# Sheet_CL-TPI-01.net
KiCad netlist of a schematic drawn in Altium Designer
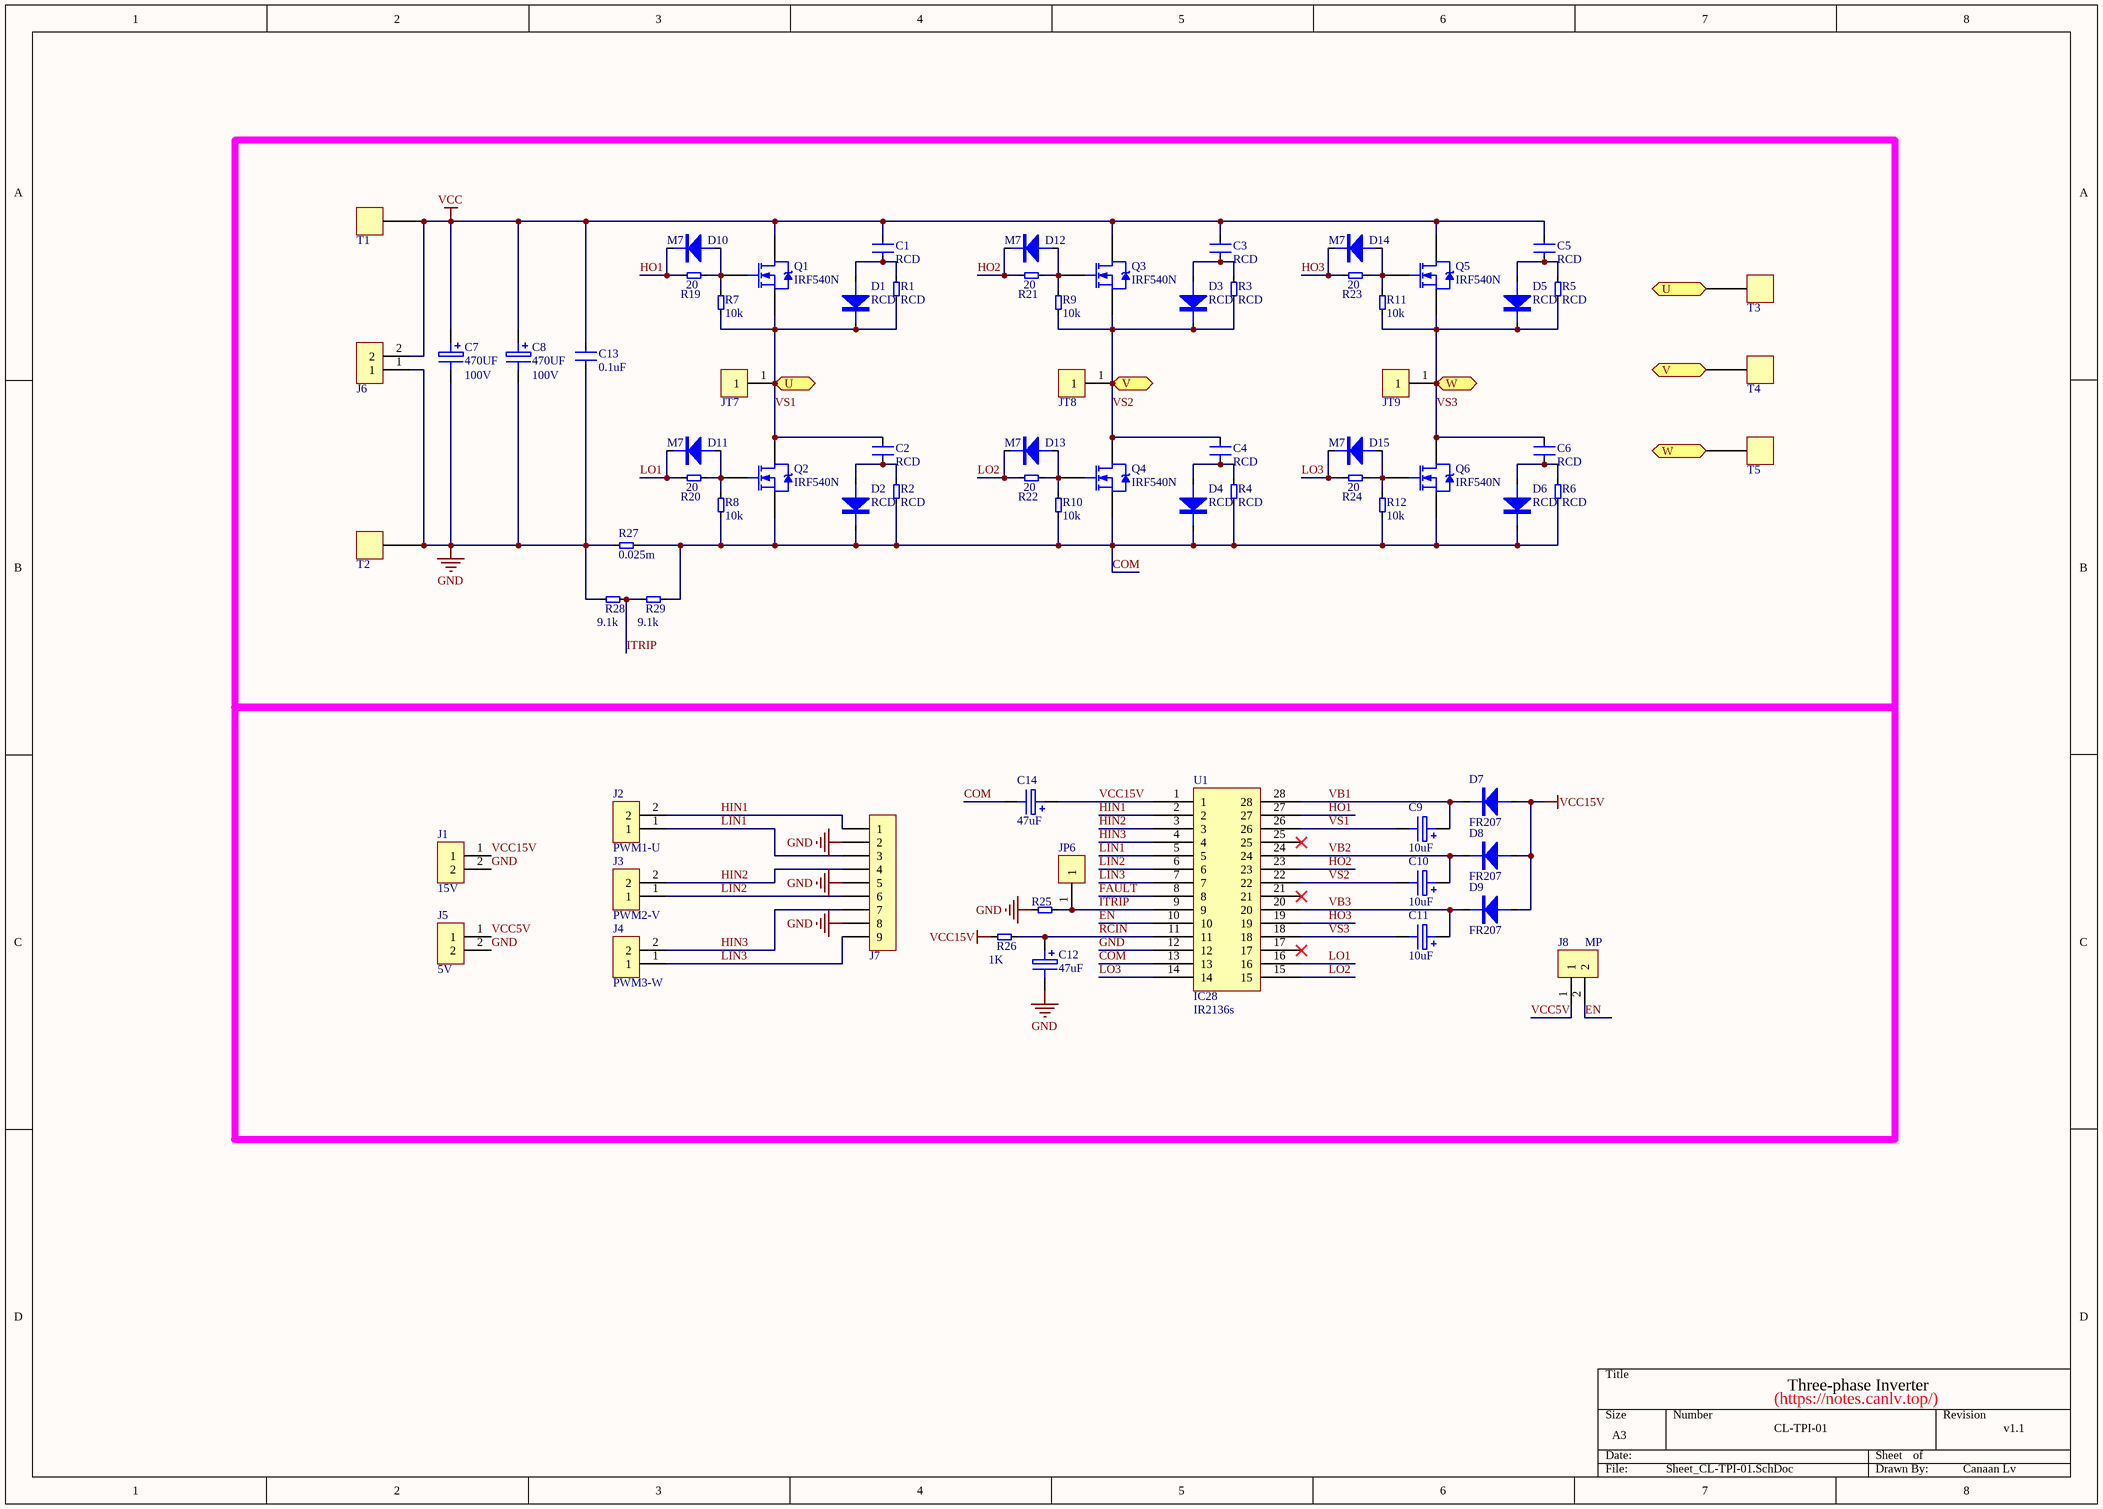
[diagram p0: Sheet_CL-TPI-01.SchDoc]

(export (version "E")
  (design (tool "Eeschema 10.0.6"))
  (components
    (comp (ref "C1") (value "RCD") (footprint "C0805") (libsource (lib "电容") (part "C贴片电容")))
    (comp (ref "C2") (value "RCD") (footprint "C0805") (libsource (lib "电容") (part "C贴片电容")))
    (comp (ref "C3") (value "RCD") (footprint "C0805") (libsource (lib "电容") (part "C贴片电容")))
    (comp (ref "C4") (value "RCD") (footprint "C0805") (libsource (lib "电容") (part "C贴片电容")))
    (comp (ref "C5") (value "RCD") (footprint "C0805") (libsource (lib "电容") (part "C贴片电容")))
    (comp (ref "C6") (value "RCD") (footprint "C0805") (libsource (lib "电容") (part "C贴片电容")))
    (comp (ref "C7")
      (value "470UF")
      (footprint "CZ16X25")
      (fields (field (name "ALTIUM_UNNAMED_1") "100V"))
      (libsource (lib "电容") (part "C直插电容"))
    )
    (comp (ref "C8")
      (value "470UF")
      (footprint "CZ16X25")
      (fields (field (name "ALTIUM_UNNAMED_1") "100V"))
      (libsource (lib "电容") (part "C直插电容"))
    )
    (comp (ref "C9") (value "10uF") (footprint "CZ0.50/25V47U") (libsource (lib "电容") (part "C直插电容")))
    (comp (ref "C10") (value "10uF") (footprint "CZ0.50/25V47U") (libsource (lib "电容") (part "C直插电容")))
    (comp (ref "C11") (value "10uF") (footprint "CZ0.50/25V47U") (libsource (lib "电容") (part "C直插电容")))
    (comp (ref "C12") (value "47uF") (footprint "CZ0.50/25V47U") (libsource (lib "电容") (part "C直插电容")))
    (comp (ref "C13") (value "0.1uF") (footprint "C0805") (libsource (lib "电容") (part "C贴片电容")))
    (comp (ref "C14") (value "47uF") (footprint "CZ0.50/25V47U") (libsource (lib "电容") (part "C直插电容")))
    (comp (ref "D1") (value "RCD") (footprint "SMA-1") (libsource (lib "二极管") (part "0805D")))
    (comp (ref "D2") (value "RCD") (footprint "SMA-1") (libsource (lib "二极管") (part "0805D")))
    (comp (ref "D3") (value "RCD") (footprint "SMA-1") (libsource (lib "二极管") (part "0805D")))
    (comp (ref "D4") (value "RCD") (footprint "SMA-1") (libsource (lib "二极管") (part "0805D")))
    (comp (ref "D5") (value "RCD") (footprint "SMA-1") (libsource (lib "二极管") (part "0805D")))
    (comp (ref "D6") (value "RCD") (footprint "SMA-1") (libsource (lib "二极管") (part "0805D")))
    (comp (ref "D7") (value "FR207") (footprint "DO-41-2") (libsource (lib "二极管") (part "DO-41")))
    (comp (ref "D8") (value "FR207") (footprint "DO-41-2") (libsource (lib "二极管") (part "DO-41")))
    (comp (ref "D9") (value "FR207") (footprint "DO-41-2") (libsource (lib "二极管") (part "DO-41")))
    (comp (ref "D10") (value "M7") (footprint "SMA-1") (libsource (lib "") (part "0805D_1")))
    (comp (ref "D11") (value "M7") (footprint "SMA-1") (libsource (lib "") (part "0805D_1")))
    (comp (ref "D12") (value "M7") (footprint "SMA-1") (libsource (lib "") (part "0805D_1")))
    (comp (ref "D13") (value "M7") (footprint "SMA-1") (libsource (lib "") (part "0805D_1")))
    (comp (ref "D14") (value "M7") (footprint "SMA-1") (libsource (lib "") (part "0805D_1")))
    (comp (ref "D15") (value "M7") (footprint "SMA-1") (libsource (lib "") (part "0805D_1")))
    (comp (ref "J1") (value "15V") (footprint "2.54XH接插件2P") (libsource (lib "") (part "SIP-2_2")))
    (comp (ref "J2") (value "PWM1-U") (footprint "2.54XH接插件2P") (libsource (lib "接插件") (part "SIP-2")))
    (comp (ref "J3") (value "PWM2-V") (footprint "2.54XH接插件2P") (libsource (lib "接插件") (part "SIP-2")))
    (comp (ref "J4") (value "PWM3-W") (footprint "2.54XH接插件2P") (libsource (lib "接插件") (part "SIP-2")))
    (comp (ref "J5") (value "5V") (footprint "2.54XH接插件2P") (libsource (lib "") (part "SIP-2_2")))
    (comp (ref "J6") (value "SIP-2") (footprint "2.54XH接插件2P") (libsource (lib "接插件") (part "SIP-2")))
    (comp (ref "J7") (value "SIP-9") (footprint "2.54排针1X9") (libsource (lib "接插件") (part "SIP-9")))
    (comp (ref "J8") (value "MP") (footprint "2.54排针1X2") (libsource (lib "") (part "SIP-2_1")))
    (comp (ref "JP6") (value "SIP-1") (footprint "2.54排针1X1") (libsource (lib "接插件") (part "SIP-1")))
    (comp (ref "JT7") (value "SIP-1") (footprint "2.54排针1X1") (libsource (lib "") (part "SIP-1_1")))
    (comp (ref "JT8") (value "SIP-1") (footprint "2.54排针1X1") (libsource (lib "") (part "SIP-1_1")))
    (comp (ref "JT9") (value "SIP-1") (footprint "2.54排针1X1") (libsource (lib "") (part "SIP-1_1")))
    (comp (ref "Q1")
      (value "IRF540N")
      (footprint "TO-220AB")
      (description "HEXFET Power MOSFET")
      (fields (field (name "PUBLISHER") "Altium Limited"))
      (libsource (lib "IR Discrete MOSFET - Power") (part "IRF540N"))
    )
    (comp (ref "Q2")
      (value "IRF540N")
      (footprint "TO-220AB")
      (description "HEXFET Power MOSFET")
      (fields (field (name "PUBLISHER") "Altium Limited"))
      (libsource (lib "IR Discrete MOSFET - Power") (part "IRF540N"))
    )
    (comp (ref "Q3")
      (value "IRF540N")
      (footprint "TO-220AB")
      (description "HEXFET Power MOSFET")
      (fields (field (name "PUBLISHER") "Altium Limited"))
      (libsource (lib "IR Discrete MOSFET - Power") (part "IRF540N"))
    )
    (comp (ref "Q4")
      (value "IRF540N")
      (footprint "TO-220AB")
      (description "HEXFET Power MOSFET")
      (fields (field (name "PUBLISHER") "Altium Limited"))
      (libsource (lib "IR Discrete MOSFET - Power") (part "IRF540N"))
    )
    (comp (ref "Q5")
      (value "IRF540N")
      (footprint "TO-220AB")
      (description "HEXFET Power MOSFET")
      (fields (field (name "PUBLISHER") "Altium Limited"))
      (libsource (lib "IR Discrete MOSFET - Power") (part "IRF540N"))
    )
    (comp (ref "Q6")
      (value "IRF540N")
      (footprint "TO-220AB")
      (description "HEXFET Power MOSFET")
      (fields (field (name "PUBLISHER") "Altium Limited"))
      (libsource (lib "IR Discrete MOSFET - Power") (part "IRF540N"))
    )
    (comp (ref "R1") (value "RCD") (footprint "R0805") (libsource (lib "电阻") (part "R贴片电阻")))
    (comp (ref "R2") (value "RCD") (footprint "R0805") (libsource (lib "电阻") (part "R贴片电阻")))
    (comp (ref "R3") (value "RCD") (footprint "R0805") (libsource (lib "电阻") (part "R贴片电阻")))
    (comp (ref "R4") (value "RCD") (footprint "R0805") (libsource (lib "电阻") (part "R贴片电阻")))
    (comp (ref "R5") (value "RCD") (footprint "R0805") (libsource (lib "电阻") (part "R贴片电阻")))
    (comp (ref "R6") (value "RCD") (footprint "R0805") (libsource (lib "电阻") (part "R贴片电阻")))
    (comp (ref "R7") (value "10k") (footprint "R0805") (libsource (lib "电阻") (part "R贴片电阻")))
    (comp (ref "R8") (value "10k") (footprint "R0805") (libsource (lib "电阻") (part "R贴片电阻")))
    (comp (ref "R9") (value "10k") (footprint "R0805") (libsource (lib "电阻") (part "R贴片电阻")))
    (comp (ref "R10") (value "10k") (footprint "R0805") (libsource (lib "电阻") (part "R贴片电阻")))
    (comp (ref "R11") (value "10k") (footprint "R0805") (libsource (lib "电阻") (part "R贴片电阻")))
    (comp (ref "R12") (value "10k") (footprint "R0805") (libsource (lib "电阻") (part "R贴片电阻")))
    (comp (ref "R19") (value "20") (footprint "R0805") (libsource (lib "电阻") (part "R贴片电阻")))
    (comp (ref "R20") (value "20") (footprint "R0805") (libsource (lib "电阻") (part "R贴片电阻")))
    (comp (ref "R21") (value "20") (footprint "R0805") (libsource (lib "电阻") (part "R贴片电阻")))
    (comp (ref "R22") (value "20") (footprint "R0805") (libsource (lib "电阻") (part "R贴片电阻")))
    (comp (ref "R23") (value "20") (footprint "R0805") (libsource (lib "电阻") (part "R贴片电阻")))
    (comp (ref "R24") (value "20") (footprint "R0805") (libsource (lib "电阻") (part "R贴片电阻")))
    (comp (ref "R25") (value "~") (footprint "R0805") (libsource (lib "电阻") (part "R贴片电阻")))
    (comp (ref "R26")
      (value "~")
      (footprint "R0805")
      (fields (field (name "ALTIUM_UNNAMED_1") "1K"))
      (libsource (lib "电阻") (part "R贴片电阻"))
    )
    (comp (ref "R27") (value "0.025m") (footprint "R2512") (libsource (lib "电阻") (part "R贴片电阻")))
    (comp (ref "R28")
      (value "R贴片电阻")
      (footprint "R0805")
      (fields (field (name "ALTIUM_UNNAMED_1") "9.1k"))
      (libsource (lib "电阻") (part "R贴片电阻"))
    )
    (comp (ref "R29")
      (value "R贴片电阻")
      (footprint "R0805")
      (fields (field (name "ALTIUM_UNNAMED_1") "9.1k"))
      (libsource (lib "电阻") (part "R贴片电阻"))
    )
    (comp (ref "T1") (value "香蕉头接线柱") (footprint "香蕉接线柱Red_6mm") (libsource (lib "接插件") (part "香蕉头接线柱")))
    (comp (ref "T2") (value "香蕉头接线柱") (footprint "香蕉接线柱Black_6mm") (libsource (lib "接插件") (part "香蕉头接线柱")))
    (comp (ref "T3") (value "香蕉头接线柱") (footprint "香蕉接线柱Black_6mm") (libsource (lib "") (part "香蕉头接线柱_1")))
    (comp (ref "T4") (value "香蕉头接线柱") (footprint "香蕉接线柱Black_6mm") (libsource (lib "") (part "香蕉头接线柱_1")))
    (comp (ref "T5") (value "香蕉头接线柱") (footprint "香蕉接线柱Black_6mm") (libsource (lib "") (part "香蕉头接线柱_1")))
    (comp (ref "U1")
      (value "IC28")
      (footprint "SOIC-28_300MIL")
      (fields (field (name "ALTIUM_UNNAMED_1") "IR2136s"))
      (libsource (lib "集成块") (part "IC28"))
    )
  )
  (nets
    (net (code "1") (name "/COM") (class "Default")
      (node (ref "C14") (pin "2") (pinfunction "2_2") (pintype "passive"))
      (node (ref "D2") (pin "K") (pinfunction "2_K") (pintype "passive"))
      (node (ref "D4") (pin "K") (pinfunction "2_K") (pintype "passive"))
      (node (ref "D6") (pin "K") (pinfunction "2_K") (pintype "passive"))
      (node (ref "Q2") (pin "3") (pinfunction "S_3") (pintype "passive"))
      (node (ref "Q4") (pin "3") (pinfunction "S_3") (pintype "passive"))
      (node (ref "Q6") (pin "3") (pinfunction "S_3") (pintype "passive"))
      (node (ref "R10") (pin "1") (pinfunction "1_1") (pintype "passive"))
      (node (ref "R12") (pin "1") (pinfunction "1_1") (pintype "passive"))
      (node (ref "R2") (pin "1") (pinfunction "1_1") (pintype "passive"))
      (node (ref "R27") (pin "2") (pinfunction "2_2") (pintype "passive"))
      (node (ref "R29") (pin "2") (pinfunction "2_2") (pintype "passive"))
      (node (ref "R4") (pin "1") (pinfunction "1_1") (pintype "passive"))
      (node (ref "R6") (pin "1") (pinfunction "1_1") (pintype "passive"))
      (node (ref "R8") (pin "1") (pinfunction "1_1") (pintype "passive"))
      (node (ref "U1") (pin "13") (pinfunction "13_13") (pintype "passive"))
    )
    (net (code "2") (name "/EN") (class "Default")
      (node (ref "J8") (pin "2") (pinfunction "2_2") (pintype "passive"))
      (node (ref "U1") (pin "10") (pinfunction "10_10") (pintype "passive"))
    )
    (net (code "3") (name "/FAULT") (class "Default")
      (node (ref "U1") (pin "8") (pinfunction "8_8") (pintype "passive"))
    )
    (net (code "4") (name "/HIN1") (class "Default")
      (node (ref "J2") (pin "2") (pinfunction "2_2") (pintype "passive"))
      (node (ref "J7") (pin "1") (pinfunction "1_1") (pintype "passive"))
      (node (ref "U1") (pin "2") (pinfunction "2_2") (pintype "passive"))
    )
    (net (code "5") (name "/HIN2") (class "Default")
      (node (ref "J3") (pin "2") (pinfunction "2_2") (pintype "passive"))
      (node (ref "J7") (pin "4") (pinfunction "4_4") (pintype "passive"))
      (node (ref "U1") (pin "3") (pinfunction "3_3") (pintype "passive"))
    )
    (net (code "6") (name "/HIN3") (class "Default")
      (node (ref "J4") (pin "2") (pinfunction "2_2") (pintype "passive"))
      (node (ref "J7") (pin "7") (pinfunction "7_7") (pintype "passive"))
      (node (ref "U1") (pin "4") (pinfunction "4_4") (pintype "passive"))
    )
    (net (code "7") (name "/HO1") (class "Default")
      (node (ref "D10") (pin "K") (pinfunction "2_K") (pintype "passive"))
      (node (ref "R19") (pin "1") (pinfunction "1_1") (pintype "passive"))
      (node (ref "U1") (pin "27") (pinfunction "27_27") (pintype "passive"))
    )
    (net (code "8") (name "/HO2") (class "Default")
      (node (ref "D12") (pin "K") (pinfunction "2_K") (pintype "passive"))
      (node (ref "R21") (pin "1") (pinfunction "1_1") (pintype "passive"))
      (node (ref "U1") (pin "23") (pinfunction "23_23") (pintype "passive"))
    )
    (net (code "9") (name "/HO3") (class "Default")
      (node (ref "D14") (pin "K") (pinfunction "2_K") (pintype "passive"))
      (node (ref "R23") (pin "1") (pinfunction "1_1") (pintype "passive"))
      (node (ref "U1") (pin "19") (pinfunction "19_19") (pintype "passive"))
    )
    (net (code "10") (name "/ITRIP") (class "Default")
      (node (ref "JP6") (pin "1") (pinfunction "1_1") (pintype "passive"))
      (node (ref "R25") (pin "2") (pinfunction "2_2") (pintype "passive"))
      (node (ref "R28") (pin "2") (pinfunction "2_2") (pintype "passive"))
      (node (ref "R29") (pin "1") (pinfunction "1_1") (pintype "passive"))
      (node (ref "U1") (pin "9") (pinfunction "9_9") (pintype "passive"))
    )
    (net (code "11") (name "/LIN1") (class "Default")
      (node (ref "J2") (pin "1") (pinfunction "1_1") (pintype "passive"))
      (node (ref "J7") (pin "3") (pinfunction "3_3") (pintype "passive"))
      (node (ref "U1") (pin "5") (pinfunction "5_5") (pintype "passive"))
    )
    (net (code "12") (name "/LIN2") (class "Default")
      (node (ref "J3") (pin "1") (pinfunction "1_1") (pintype "passive"))
      (node (ref "J7") (pin "6") (pinfunction "6_6") (pintype "passive"))
      (node (ref "U1") (pin "6") (pinfunction "6_6") (pintype "passive"))
    )
    (net (code "13") (name "/LIN3") (class "Default")
      (node (ref "J4") (pin "1") (pinfunction "1_1") (pintype "passive"))
      (node (ref "J7") (pin "9") (pinfunction "9_9") (pintype "passive"))
      (node (ref "U1") (pin "7") (pinfunction "7_7") (pintype "passive"))
    )
    (net (code "14") (name "/LO1") (class "Default")
      (node (ref "D11") (pin "K") (pinfunction "2_K") (pintype "passive"))
      (node (ref "R20") (pin "1") (pinfunction "1_1") (pintype "passive"))
      (node (ref "U1") (pin "16") (pinfunction "16_16") (pintype "passive"))
    )
    (net (code "15") (name "/LO2") (class "Default")
      (node (ref "D13") (pin "K") (pinfunction "2_K") (pintype "passive"))
      (node (ref "R22") (pin "1") (pinfunction "1_1") (pintype "passive"))
      (node (ref "U1") (pin "15") (pinfunction "15_15") (pintype "passive"))
    )
    (net (code "16") (name "/LO3") (class "Default")
      (node (ref "D15") (pin "K") (pinfunction "2_K") (pintype "passive"))
      (node (ref "R24") (pin "1") (pinfunction "1_1") (pintype "passive"))
      (node (ref "U1") (pin "14") (pinfunction "14_14") (pintype "passive"))
    )
    (net (code "17") (name "/RCIN") (class "Default")
      (node (ref "C12") (pin "1") (pinfunction "1_1") (pintype "passive"))
      (node (ref "R26") (pin "2") (pinfunction "2_2") (pintype "passive"))
      (node (ref "U1") (pin "11") (pinfunction "11_11") (pintype "passive"))
    )
    (net (code "18") (name "/VB1") (class "Default")
      (node (ref "C9") (pin "1") (pinfunction "1_1") (pintype "passive"))
      (node (ref "D7") (pin "K") (pinfunction "2_K") (pintype "passive"))
      (node (ref "U1") (pin "28") (pinfunction "28_28") (pintype "passive"))
    )
    (net (code "19") (name "/VB2") (class "Default")
      (node (ref "C10") (pin "1") (pinfunction "1_1") (pintype "passive"))
      (node (ref "D8") (pin "K") (pinfunction "2_K") (pintype "passive"))
      (node (ref "U1") (pin "24") (pinfunction "24_24") (pintype "passive"))
    )
    (net (code "20") (name "/VB3") (class "Default")
      (node (ref "C11") (pin "1") (pinfunction "1_1") (pintype "passive"))
      (node (ref "D9") (pin "K") (pinfunction "2_K") (pintype "passive"))
      (node (ref "U1") (pin "20") (pinfunction "20_20") (pintype "passive"))
    )
    (net (code "21") (name "/VCC5V") (class "Default")
      (node (ref "J5") (pin "1") (pinfunction "1_1") (pintype "passive"))
      (node (ref "J8") (pin "1") (pinfunction "1_1") (pintype "passive"))
    )
    (net (code "22") (name "/VS1") (class "Default")
      (node (ref "C2") (pin "1") (pinfunction "1_1") (pintype "passive"))
      (node (ref "C9") (pin "2") (pinfunction "2_2") (pintype "passive"))
      (node (ref "D1") (pin "K") (pinfunction "2_K") (pintype "passive"))
      (node (ref "JT7") (pin "1") (pinfunction "1_1") (pintype "passive"))
      (node (ref "Q1") (pin "3") (pinfunction "S_3") (pintype "passive"))
      (node (ref "Q2") (pin "2") (pinfunction "D_2") (pintype "passive"))
      (node (ref "R1") (pin "1") (pinfunction "1_1") (pintype "passive"))
      (node (ref "R7") (pin "1") (pinfunction "1_1") (pintype "passive"))
      (node (ref "T3") (pin "1") (pinfunction "1_1") (pintype "passive"))
      (node (ref "U1") (pin "26") (pinfunction "26_26") (pintype "passive"))
    )
    (net (code "23") (name "/VS2") (class "Default")
      (node (ref "C10") (pin "2") (pinfunction "2_2") (pintype "passive"))
      (node (ref "C4") (pin "1") (pinfunction "1_1") (pintype "passive"))
      (node (ref "D3") (pin "K") (pinfunction "2_K") (pintype "passive"))
      (node (ref "JT8") (pin "1") (pinfunction "1_1") (pintype "passive"))
      (node (ref "Q3") (pin "3") (pinfunction "S_3") (pintype "passive"))
      (node (ref "Q4") (pin "2") (pinfunction "D_2") (pintype "passive"))
      (node (ref "R3") (pin "1") (pinfunction "1_1") (pintype "passive"))
      (node (ref "R9") (pin "1") (pinfunction "1_1") (pintype "passive"))
      (node (ref "T4") (pin "1") (pinfunction "1_1") (pintype "passive"))
      (node (ref "U1") (pin "22") (pinfunction "22_22") (pintype "passive"))
    )
    (net (code "24") (name "/VS3") (class "Default")
      (node (ref "C11") (pin "2") (pinfunction "2_2") (pintype "passive"))
      (node (ref "C6") (pin "1") (pinfunction "1_1") (pintype "passive"))
      (node (ref "D5") (pin "K") (pinfunction "2_K") (pintype "passive"))
      (node (ref "JT9") (pin "1") (pinfunction "1_1") (pintype "passive"))
      (node (ref "Q5") (pin "3") (pinfunction "S_3") (pintype "passive"))
      (node (ref "Q6") (pin "2") (pinfunction "D_2") (pintype "passive"))
      (node (ref "R11") (pin "1") (pinfunction "1_1") (pintype "passive"))
      (node (ref "R5") (pin "1") (pinfunction "1_1") (pintype "passive"))
      (node (ref "T5") (pin "1") (pinfunction "1_1") (pintype "passive"))
      (node (ref "U1") (pin "18") (pinfunction "18_18") (pintype "passive"))
    )
    (net (code "25") (name "GND") (class "Default")
      (node (ref "C12") (pin "2") (pinfunction "2_2") (pintype "passive"))
      (node (ref "C13") (pin "2") (pinfunction "2_2") (pintype "passive"))
      (node (ref "C7") (pin "2") (pinfunction "2_2") (pintype "passive"))
      (node (ref "C8") (pin "2") (pinfunction "2_2") (pintype "passive"))
      (node (ref "J1") (pin "2") (pinfunction "2_2") (pintype "passive"))
      (node (ref "J5") (pin "2") (pinfunction "2_2") (pintype "passive"))
      (node (ref "J6") (pin "1") (pinfunction "1_1") (pintype "passive"))
      (node (ref "J7") (pin "2") (pinfunction "2_2") (pintype "passive"))
      (node (ref "J7") (pin "5") (pinfunction "5_5") (pintype "passive"))
      (node (ref "J7") (pin "8") (pinfunction "8_8") (pintype "passive"))
      (node (ref "R25") (pin "1") (pinfunction "1_1") (pintype "passive"))
      (node (ref "R27") (pin "1") (pinfunction "1_1") (pintype "passive"))
      (node (ref "R28") (pin "1") (pinfunction "1_1") (pintype "passive"))
      (node (ref "T2") (pin "1") (pinfunction "1_1") (pintype "passive"))
      (node (ref "U1") (pin "12") (pinfunction "12_12") (pintype "passive"))
    )
    (net (code "26") (name "Net-(D1-1)") (class "Default")
      (node (ref "C1") (pin "2") (pinfunction "2_2") (pintype "passive"))
      (node (ref "D1") (pin "A") (pinfunction "1_A") (pintype "passive"))
      (node (ref "R1") (pin "2") (pinfunction "2_2") (pintype "passive"))
    )
    (net (code "27") (name "Net-(D2-1)") (class "Default")
      (node (ref "C2") (pin "2") (pinfunction "2_2") (pintype "passive"))
      (node (ref "D2") (pin "A") (pinfunction "1_A") (pintype "passive"))
      (node (ref "R2") (pin "2") (pinfunction "2_2") (pintype "passive"))
    )
    (net (code "28") (name "Net-(D3-1)") (class "Default")
      (node (ref "C3") (pin "2") (pinfunction "2_2") (pintype "passive"))
      (node (ref "D3") (pin "A") (pinfunction "1_A") (pintype "passive"))
      (node (ref "R3") (pin "2") (pinfunction "2_2") (pintype "passive"))
    )
    (net (code "29") (name "Net-(D4-1)") (class "Default")
      (node (ref "C4") (pin "2") (pinfunction "2_2") (pintype "passive"))
      (node (ref "D4") (pin "A") (pinfunction "1_A") (pintype "passive"))
      (node (ref "R4") (pin "2") (pinfunction "2_2") (pintype "passive"))
    )
    (net (code "30") (name "Net-(D5-1)") (class "Default")
      (node (ref "C5") (pin "2") (pinfunction "2_2") (pintype "passive"))
      (node (ref "D5") (pin "A") (pinfunction "1_A") (pintype "passive"))
      (node (ref "R5") (pin "2") (pinfunction "2_2") (pintype "passive"))
    )
    (net (code "31") (name "Net-(D6-1)") (class "Default")
      (node (ref "C6") (pin "2") (pinfunction "2_2") (pintype "passive"))
      (node (ref "D6") (pin "A") (pinfunction "1_A") (pintype "passive"))
      (node (ref "R6") (pin "2") (pinfunction "2_2") (pintype "passive"))
    )
    (net (code "32") (name "Net-(D10-1)") (class "Default")
      (node (ref "D10") (pin "A") (pinfunction "1_A") (pintype "passive"))
      (node (ref "Q1") (pin "1") (pinfunction "G_1") (pintype "passive"))
      (node (ref "R19") (pin "2") (pinfunction "2_2") (pintype "passive"))
      (node (ref "R7") (pin "2") (pinfunction "2_2") (pintype "passive"))
    )
    (net (code "33") (name "Net-(D11-1)") (class "Default")
      (node (ref "D11") (pin "A") (pinfunction "1_A") (pintype "passive"))
      (node (ref "Q2") (pin "1") (pinfunction "G_1") (pintype "passive"))
      (node (ref "R20") (pin "2") (pinfunction "2_2") (pintype "passive"))
      (node (ref "R8") (pin "2") (pinfunction "2_2") (pintype "passive"))
    )
    (net (code "34") (name "Net-(D12-1)") (class "Default")
      (node (ref "D12") (pin "A") (pinfunction "1_A") (pintype "passive"))
      (node (ref "Q3") (pin "1") (pinfunction "G_1") (pintype "passive"))
      (node (ref "R21") (pin "2") (pinfunction "2_2") (pintype "passive"))
      (node (ref "R9") (pin "2") (pinfunction "2_2") (pintype "passive"))
    )
    (net (code "35") (name "Net-(D13-1)") (class "Default")
      (node (ref "D13") (pin "A") (pinfunction "1_A") (pintype "passive"))
      (node (ref "Q4") (pin "1") (pinfunction "G_1") (pintype "passive"))
      (node (ref "R10") (pin "2") (pinfunction "2_2") (pintype "passive"))
      (node (ref "R22") (pin "2") (pinfunction "2_2") (pintype "passive"))
    )
    (net (code "36") (name "Net-(D14-1)") (class "Default")
      (node (ref "D14") (pin "A") (pinfunction "1_A") (pintype "passive"))
      (node (ref "Q5") (pin "1") (pinfunction "G_1") (pintype "passive"))
      (node (ref "R11") (pin "2") (pinfunction "2_2") (pintype "passive"))
      (node (ref "R23") (pin "2") (pinfunction "2_2") (pintype "passive"))
    )
    (net (code "37") (name "Net-(D15-1)") (class "Default")
      (node (ref "D15") (pin "A") (pinfunction "1_A") (pintype "passive"))
      (node (ref "Q6") (pin "1") (pinfunction "G_1") (pintype "passive"))
      (node (ref "R12") (pin "2") (pinfunction "2_2") (pintype "passive"))
      (node (ref "R24") (pin "2") (pinfunction "2_2") (pintype "passive"))
    )
    (net (code "38") (name "VCC") (class "Default")
      (node (ref "C1") (pin "1") (pinfunction "1_1") (pintype "passive"))
      (node (ref "C13") (pin "1") (pinfunction "1_1") (pintype "passive"))
      (node (ref "C3") (pin "1") (pinfunction "1_1") (pintype "passive"))
      (node (ref "C5") (pin "1") (pinfunction "1_1") (pintype "passive"))
      (node (ref "C7") (pin "1") (pinfunction "1_1") (pintype "passive"))
      (node (ref "C8") (pin "1") (pinfunction "1_1") (pintype "passive"))
      (node (ref "J6") (pin "2") (pinfunction "2_2") (pintype "passive"))
      (node (ref "Q1") (pin "2") (pinfunction "D_2") (pintype "passive"))
      (node (ref "Q3") (pin "2") (pinfunction "D_2") (pintype "passive"))
      (node (ref "Q5") (pin "2") (pinfunction "D_2") (pintype "passive"))
      (node (ref "T1") (pin "1") (pinfunction "1_1") (pintype "passive"))
    )
    (net (code "39") (name "VCC15V") (class "Default")
      (node (ref "C14") (pin "1") (pinfunction "1_1") (pintype "passive"))
      (node (ref "D7") (pin "A") (pinfunction "1_A") (pintype "passive"))
      (node (ref "D8") (pin "A") (pinfunction "1_A") (pintype "passive"))
      (node (ref "D9") (pin "A") (pinfunction "1_A") (pintype "passive"))
      (node (ref "J1") (pin "1") (pinfunction "1_1") (pintype "passive"))
      (node (ref "R26") (pin "1") (pinfunction "1_1") (pintype "passive"))
      (node (ref "U1") (pin "1") (pinfunction "1_1") (pintype "passive"))
    )
    (net (code "40") (name "unconnected-(U1-Pad17)") (class "Default")
      (node (ref "U1") (pin "17") (pinfunction "17_17") (pintype "passive+no_connect"))
    )
    (net (code "41") (name "unconnected-(U1-Pad21)") (class "Default")
      (node (ref "U1") (pin "21") (pinfunction "21_21") (pintype "passive+no_connect"))
    )
    (net (code "42") (name "unconnected-(U1-Pad25)") (class "Default")
      (node (ref "U1") (pin "25") (pinfunction "25_25") (pintype "passive+no_connect"))
    )
  )
)
